# sp0256_dcf77.net
KiCad netlist of a schematic drawn in EAGLE
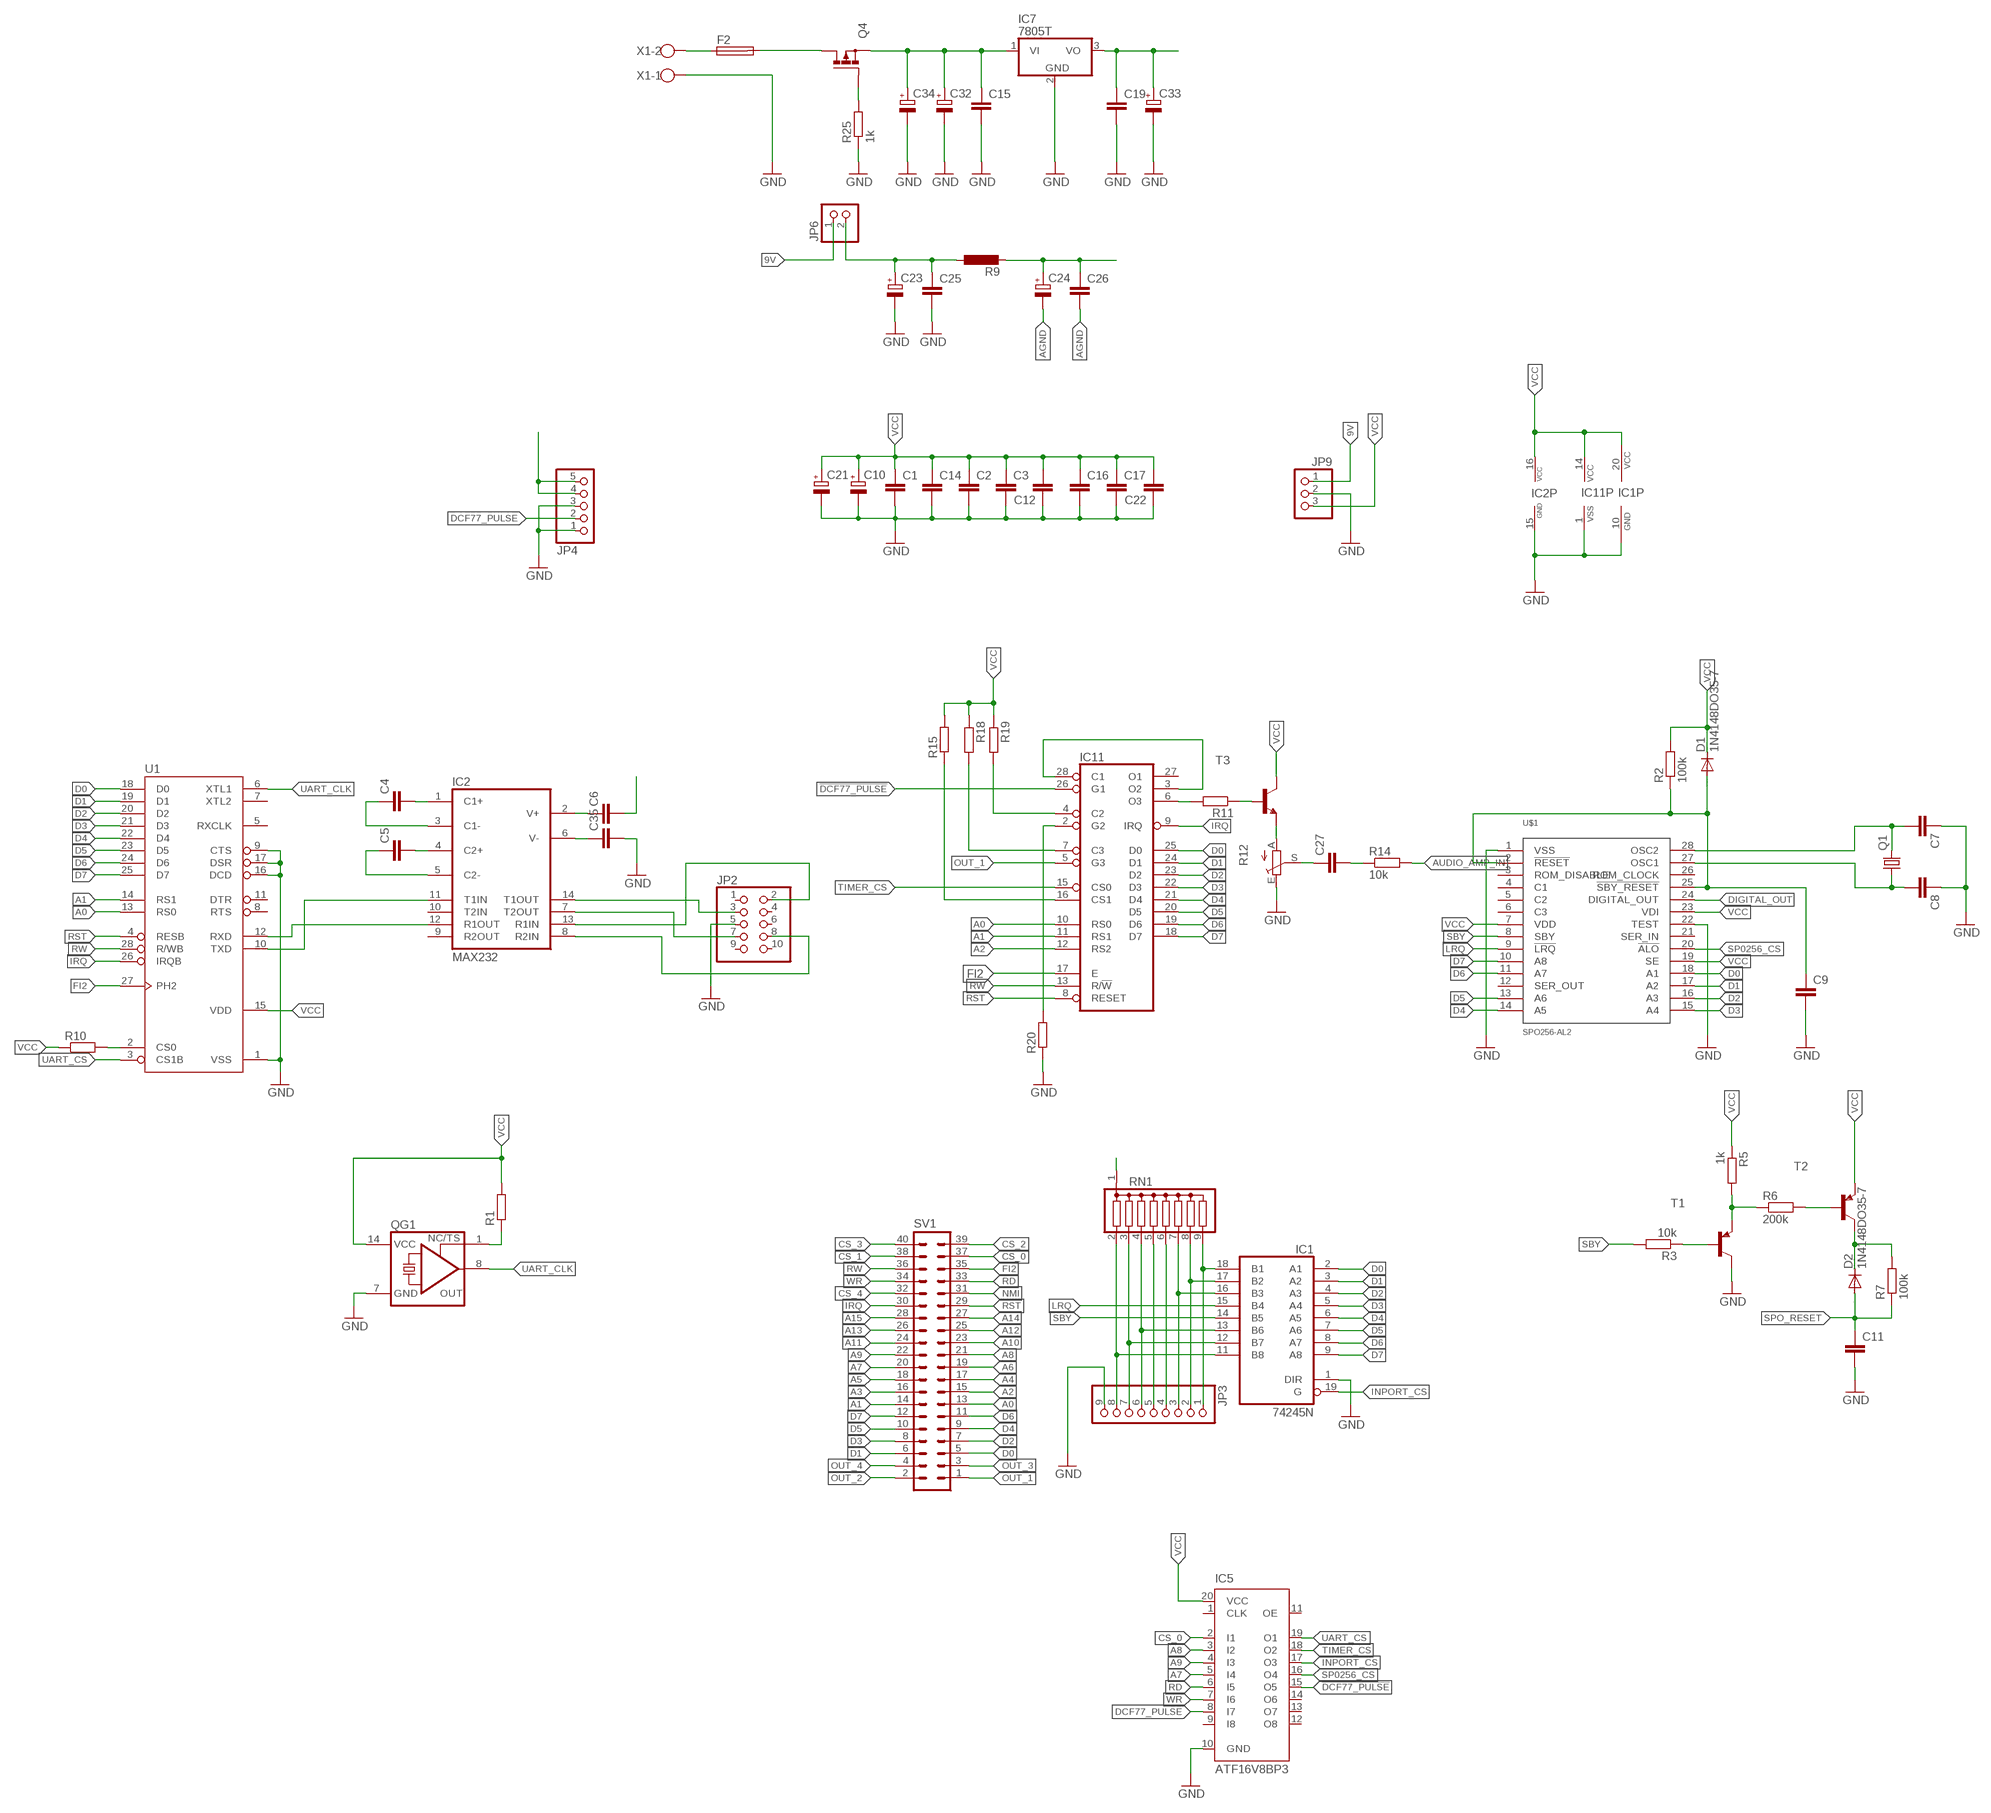
[diagram p0: schematic, sheet 1, part 1 of 2]
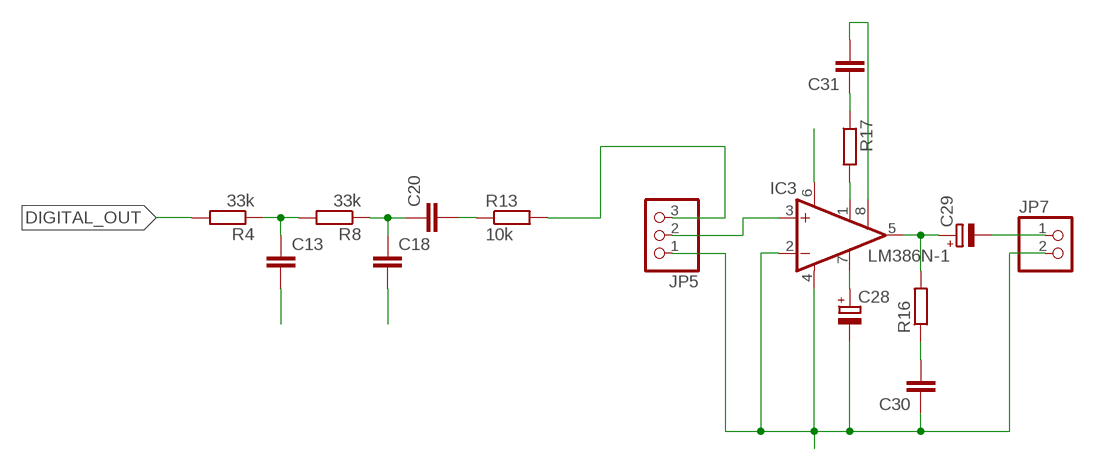
[diagram p1: schematic, sheet 1, part 2 of 2]

(export (version "E")
  (design (tool "Eeschema 10.0.6"))
  (components
    (comp (ref "C1")
      (value "C-EUC1206")
      (footprint "eagle-import:C1206")
      (libsource (lib "eagle-import") (part "C-EUC1206"))
    )
    (comp (ref "C2")
      (value "C-EUC1206")
      (footprint "eagle-import:C1206")
      (libsource (lib "eagle-import") (part "C-EUC1206"))
    )
    (comp (ref "C3")
      (value "C-EUC1206")
      (footprint "eagle-import:C1206")
      (libsource (lib "eagle-import") (part "C-EUC1206"))
    )
    (comp (ref "C4")
      (value "C-EUC0603")
      (footprint "eagle-import:C0603")
      (libsource (lib "eagle-import") (part "C-EUC0603"))
    )
    (comp (ref "C5")
      (value "C-EUC0603")
      (footprint "eagle-import:C0603")
      (libsource (lib "eagle-import") (part "C-EUC0603"))
    )
    (comp (ref "C6")
      (value "C-EUC0603")
      (footprint "eagle-import:C0603")
      (libsource (lib "eagle-import") (part "C-EUC0603"))
    )
    (comp (ref "C7")
      (value "C-EUC0603")
      (footprint "eagle-import:C0603")
      (libsource (lib "eagle-import") (part "C-EUC0603"))
    )
    (comp (ref "C8")
      (value "C-EUC0603")
      (footprint "eagle-import:C0603")
      (libsource (lib "eagle-import") (part "C-EUC0603"))
    )
    (comp (ref "C9")
      (value "C-EUC0603")
      (footprint "eagle-import:C0603")
      (libsource (lib "eagle-import") (part "C-EUC0603"))
    )
    (comp (ref "C10")
      (value "CPOL-EUE5-10.5")
      (footprint "eagle-import:E5-10,5")
      (libsource (lib "eagle-import") (part "CPOL-EUE5-10.5"))
    )
    (comp (ref "C11")
      (value "C-EUC0603")
      (footprint "eagle-import:C0603")
      (libsource (lib "eagle-import") (part "C-EUC0603"))
    )
    (comp (ref "C12")
      (value "C-EUC0603")
      (footprint "eagle-import:C0603")
      (libsource (lib "eagle-import") (part "C-EUC0603"))
    )
    (comp (ref "C13")
      (value "C-EUC0603")
      (footprint "eagle-import:C0603")
      (libsource (lib "eagle-import") (part "C-EUC0603"))
    )
    (comp (ref "C14")
      (value "C-EUC1206")
      (footprint "eagle-import:C1206")
      (libsource (lib "eagle-import") (part "C-EUC1206"))
    )
    (comp (ref "C15")
      (value "C-EUC1206")
      (footprint "eagle-import:C1206")
      (libsource (lib "eagle-import") (part "C-EUC1206"))
    )
    (comp (ref "C16")
      (value "C-EUC1206")
      (footprint "eagle-import:C1206")
      (libsource (lib "eagle-import") (part "C-EUC1206"))
    )
    (comp (ref "C17")
      (value "C-EUC1206")
      (footprint "eagle-import:C1206")
      (libsource (lib "eagle-import") (part "C-EUC1206"))
    )
    (comp (ref "C18")
      (value "C-EUC0603")
      (footprint "eagle-import:C0603")
      (libsource (lib "eagle-import") (part "C-EUC0603"))
    )
    (comp (ref "C19")
      (value "C-EUC1206")
      (footprint "eagle-import:C1206")
      (libsource (lib "eagle-import") (part "C-EUC1206"))
    )
    (comp (ref "C20")
      (value "C-EUC0603")
      (footprint "eagle-import:C0603")
      (libsource (lib "eagle-import") (part "C-EUC0603"))
    )
    (comp (ref "C21")
      (value "CPOL-EUSMCB")
      (footprint "eagle-import:SMC_B")
      (libsource (lib "eagle-import") (part "CPOL-EUSMCB"))
    )
    (comp (ref "C22")
      (value "C-EUC0603")
      (footprint "eagle-import:C0603")
      (libsource (lib "eagle-import") (part "C-EUC0603"))
    )
    (comp (ref "C23")
      (value "CPOL-EUE5-10.5")
      (footprint "eagle-import:E5-10,5")
      (libsource (lib "eagle-import") (part "CPOL-EUE5-10.5"))
    )
    (comp (ref "C24")
      (value "CPOL-EUE5-10.5")
      (footprint "eagle-import:E5-10,5")
      (libsource (lib "eagle-import") (part "CPOL-EUE5-10.5"))
    )
    (comp (ref "C25")
      (value "C-EUC1206")
      (footprint "eagle-import:C1206")
      (libsource (lib "eagle-import") (part "C-EUC1206"))
    )
    (comp (ref "C26")
      (value "C-EUC1206")
      (footprint "eagle-import:C1206")
      (libsource (lib "eagle-import") (part "C-EUC1206"))
    )
    (comp (ref "C27")
      (value "C-EUC0603")
      (footprint "eagle-import:C0603")
      (libsource (lib "eagle-import") (part "C-EUC0603"))
    )
    (comp (ref "C28")
      (value "CPOL-EUSMCB")
      (footprint "eagle-import:SMC_B")
      (libsource (lib "eagle-import") (part "CPOL-EUSMCB"))
    )
    (comp (ref "C29")
      (value "CPOL-EUE5-10.5")
      (footprint "eagle-import:E5-10,5")
      (libsource (lib "eagle-import") (part "CPOL-EUE5-10.5"))
    )
    (comp (ref "C30")
      (value "C-EUC0603")
      (footprint "eagle-import:C0603")
      (libsource (lib "eagle-import") (part "C-EUC0603"))
    )
    (comp (ref "C31")
      (value "C-EUC0603")
      (footprint "eagle-import:C0603")
      (libsource (lib "eagle-import") (part "C-EUC0603"))
    )
    (comp (ref "C32")
      (value "CPOL-EUE5-10.5")
      (footprint "eagle-import:E5-10,5")
      (libsource (lib "eagle-import") (part "CPOL-EUE5-10.5"))
    )
    (comp (ref "C33")
      (value "CPOL-EUE5-10.5")
      (footprint "eagle-import:E5-10,5")
      (libsource (lib "eagle-import") (part "CPOL-EUE5-10.5"))
    )
    (comp (ref "C34")
      (value "CPOL-EUE5-10.5")
      (footprint "eagle-import:E5-10,5")
      (libsource (lib "eagle-import") (part "CPOL-EUE5-10.5"))
    )
    (comp (ref "C35")
      (value "C-EUC0603")
      (footprint "eagle-import:C0603")
      (libsource (lib "eagle-import") (part "C-EUC0603"))
    )
    (comp (ref "D1")
      (value "1N4148DO35-7")
      (footprint "eagle-import:DO35-7")
      (libsource (lib "eagle-import") (part "1N4148DO35-7"))
    )
    (comp (ref "D2")
      (value "1N4148DO35-7")
      (footprint "eagle-import:DO35-7")
      (libsource (lib "eagle-import") (part "1N4148DO35-7"))
    )
    (comp (ref "F2")
      (value "SH22,5")
      (footprint "eagle-import:SH22,5")
      (fields
        (field (name "MF") "SCHURTER")
        (field (name "MPN") "0031.8201")
        (field (name "MF_1") "SCHURTER")
        (field (name "MPN_1") "0031.8201")
        (field (name "OC_FARNELL") "1162740")
        (field (name "OC_NEWARK") "96F8317")
      )
      (libsource (lib "eagle-import") (part "SH22,5"))
    )
    (comp (ref "IC1")
      (value "74245N")
      (footprint "eagle-import:DIL20")
      (libsource (lib "eagle-import") (part "74245NLS"))
    )
    (comp (ref "IC2")
      (value "MAX232")
      (footprint "eagle-import:DIL16")
      (fields (field (name "MF") "MAXIM") (field (name "MPN") "MAX232ACPE+"))
      (libsource (lib "eagle-import") (part "MAX232"))
    )
    (comp (ref "IC3")
      (value "LM386N-1")
      (footprint "eagle-import:DIL08")
      (libsource (lib "eagle-import") (part "LM386?-N1"))
    )
    (comp (ref "IC5")
      (value "ATF16V8BP3")
      (footprint "eagle-import:DIL20")
      (fields (field (name "MPN") "ATF16V8CZ-15PU"))
      (libsource (lib "eagle-import") (part "ATF16V8BP3"))
    )
    (comp (ref "IC7")
      (value "7805T")
      (footprint "eagle-import:TO220H")
      (libsource (lib "eagle-import") (part "78T05"))
    )
    (comp (ref "IC11")
      (value "6840")
      (footprint "eagle-import:DIL28")
      (libsource (lib "eagle-import") (part "6840"))
    )
    (comp (ref "JP2")
      (value "PINHD-2X5")
      (footprint "eagle-import:2X05")
      (libsource (lib "eagle-import") (part "PINHD-2X5"))
    )
    (comp (ref "JP3")
      (value "PINHD-1X9")
      (footprint "eagle-import:1X09")
      (libsource (lib "eagle-import") (part "PINHD-1X9"))
    )
    (comp (ref "JP4")
      (value "PINHD-1X5")
      (footprint "eagle-import:1X05")
      (libsource (lib "eagle-import") (part "PINHD-1X5"))
    )
    (comp (ref "JP5")
      (value "PINHD-1X3")
      (footprint "eagle-import:1X03")
      (libsource (lib "eagle-import") (part "PINHD-1X3"))
    )
    (comp (ref "JP6")
      (value "PINHD-1X2")
      (footprint "eagle-import:1X02")
      (libsource (lib "eagle-import") (part "PINHD-1X2"))
    )
    (comp (ref "JP7")
      (value "PINHD-1X2")
      (footprint "eagle-import:1X02")
      (libsource (lib "eagle-import") (part "PINHD-1X2"))
    )
    (comp (ref "JP9")
      (value "PINHD-1X3/90")
      (footprint "eagle-import:1X03_90")
      (libsource (lib "eagle-import") (part "PINHD-1X3/90"))
    )
    (comp (ref "Q1")
      (value "CRYSTALHC49U-V")
      (footprint "eagle-import:HC49U-V")
      (libsource (lib "eagle-import") (part "CRYSTALHC49U-V"))
    )
    (comp (ref "Q4")
      (value "P-MOSFET-SO8")
      (footprint "eagle-import:SO-08")
      (libsource (lib "eagle-import") (part "P-MOSFET-SO8"))
    )
    (comp (ref "QG1")
      (value "XO-14")
      (footprint "eagle-import:DIL14S")
      (libsource (lib "eagle-import") (part "XO-14"))
    )
    (comp (ref "R1")
      (value "R-EU_R1206")
      (footprint "eagle-import:R1206")
      (libsource (lib "eagle-import") (part "R-EU_R1206"))
    )
    (comp (ref "R2")
      (value "100k")
      (footprint "eagle-import:0204_7")
      (libsource (lib "eagle-import") (part "R-EU_0204/7"))
    )
    (comp (ref "R3")
      (value "10k")
      (footprint "eagle-import:0204_7")
      (libsource (lib "eagle-import") (part "R-EU_0204/7"))
    )
    (comp (ref "R4")
      (value "33k")
      (footprint "eagle-import:0204_7")
      (libsource (lib "eagle-import") (part "R-EU_0204/7"))
    )
    (comp (ref "R5")
      (value "1k")
      (footprint "eagle-import:0204_5")
      (libsource (lib "eagle-import") (part "R-EU_0204/5"))
    )
    (comp (ref "R6")
      (value "200k")
      (footprint "eagle-import:R0603")
      (libsource (lib "eagle-import") (part "R-EU_R0603"))
    )
    (comp (ref "R7")
      (value "100k")
      (footprint "eagle-import:0204_7")
      (libsource (lib "eagle-import") (part "R-EU_0204/7"))
    )
    (comp (ref "R8")
      (value "33k")
      (footprint "eagle-import:0204_7")
      (libsource (lib "eagle-import") (part "R-EU_0204/7"))
    )
    (comp (ref "R9")
      (value "L-EU0204/7")
      (footprint "eagle-import:0204_7")
      (libsource (lib "eagle-import") (part "L-EU0204/7"))
    )
    (comp (ref "R10")
      (value "R-EU_R0603")
      (footprint "eagle-import:R0603")
      (libsource (lib "eagle-import") (part "R-EU_R0603"))
    )
    (comp (ref "R11")
      (value "R-EU_0204/7")
      (footprint "eagle-import:0204_7")
      (libsource (lib "eagle-import") (part "R-EU_0204/7"))
    )
    (comp (ref "R12")
      (value "TRIM_EU-CA6V")
      (footprint "eagle-import:CA6V")
      (libsource (lib "eagle-import") (part "TRIM_EU-CA6V"))
    )
    (comp (ref "R13")
      (value "10k")
      (footprint "eagle-import:R0603")
      (libsource (lib "eagle-import") (part "R-EU_R0603"))
    )
    (comp (ref "R14")
      (value "10k")
      (footprint "eagle-import:R0603")
      (libsource (lib "eagle-import") (part "R-EU_R0603"))
    )
    (comp (ref "R15")
      (value "R-EU_R0603")
      (footprint "eagle-import:R0603")
      (libsource (lib "eagle-import") (part "R-EU_R0603"))
    )
    (comp (ref "R16")
      (value "R-EU_R0603")
      (footprint "eagle-import:R0603")
      (libsource (lib "eagle-import") (part "R-EU_R0603"))
    )
    (comp (ref "R17")
      (value "R-EU_0204/7")
      (footprint "eagle-import:0204_7")
      (libsource (lib "eagle-import") (part "R-EU_0204/7"))
    )
    (comp (ref "R18")
      (value "R-EU_R0603")
      (footprint "eagle-import:R0603")
      (libsource (lib "eagle-import") (part "R-EU_R0603"))
    )
    (comp (ref "R19")
      (value "R-EU_R0603")
      (footprint "eagle-import:R0603")
      (libsource (lib "eagle-import") (part "R-EU_R0603"))
    )
    (comp (ref "R20")
      (value "R-EU_R0603")
      (footprint "eagle-import:R0603")
      (libsource (lib "eagle-import") (part "R-EU_R0603"))
    )
    (comp (ref "R25")
      (value "1k")
      (footprint "eagle-import:R0603")
      (libsource (lib "eagle-import") (part "R-EU_R0603"))
    )
    (comp (ref "RN1")
      (value "G08R")
      (footprint "eagle-import:SIL9")
      (libsource (lib "eagle-import") (part "G08R"))
    )
    (comp (ref "SV1")
      (value "ML40L")
      (footprint "eagle-import:ML40L")
      (libsource (lib "eagle-import") (part "ML40L"))
    )
    (comp (ref "T1")
      (value "MPS2907A-PNP-TO92-CBE")
      (footprint "eagle-import:TO92-CBE")
      (libsource (lib "eagle-import") (part "-PNP-TO92-CBEMPS2907A"))
    )
    (comp (ref "T2")
      (value "MPS2907A-PNP-TO92-CBE")
      (footprint "eagle-import:TO92-CBE")
      (libsource (lib "eagle-import") (part "-PNP-TO92-CBEMPS2907A"))
    )
    (comp (ref "T3")
      (value "BC550-NPN-TO92-CBE")
      (footprint "eagle-import:TO92-CBE")
      (libsource (lib "eagle-import") (part "-NPN-TO92-CBEBC550"))
    )
    (comp (ref "U$1")
      (value "SPO256-AL2")
      (footprint "eagle-import:DIL28")
      (libsource (lib "eagle-import") (part "SPO256-AL2"))
    )
    (comp (ref "U1")
      (value "G65SC51P")
      (footprint "eagle-import:DIP-28")
      (libsource (lib "eagle-import") (part "G65SC51P"))
    )
    (comp (ref "X1")
      (value "W237-102")
      (footprint "eagle-import:W237-102")
      (fields (field (name "MPN") "237-102"))
      (libsource (lib "eagle-import") (part "W237-102"))
    )
  )
  (nets
    (net (code "1") (name "/AVCC") (class "Default")
      (node (ref "C24") (pin "+") (pinfunction "+_+") (pintype "passive"))
      (node (ref "C26") (pin "1") (pinfunction "1_1") (pintype "passive"))
      (node (ref "IC3") (pin "6") (pinfunction "VS_6") (pintype "power_in"))
      (node (ref "R9") (pin "2") (pinfunction "2_2") (pintype "passive"))
    )
    (net (code "2") (name "/~{DCF77_PULSE}") (class "Default")
      (node (ref "IC11") (pin "26") (pinfunction "G1_26") (pintype "input"))
      (node (ref "IC5") (pin "15") (pinfunction "O5_15") (pintype "output"))
    )
    (net (code "3") (name "9V") (class "Default")
      (node (ref "C15") (pin "1") (pinfunction "1_1") (pintype "passive"))
      (node (ref "C32") (pin "+") (pinfunction "+_+") (pintype "passive"))
      (node (ref "C34") (pin "+") (pinfunction "+_+") (pintype "passive"))
      (node (ref "IC7") (pin "1") (pinfunction "VI_1") (pintype "input"))
      (node (ref "JP6") (pin "1") (pinfunction "1_1") (pintype "passive"))
      (node (ref "JP9") (pin "1") (pinfunction "1_1") (pintype "passive"))
      (node (ref "Q4") (pin "1") (pinfunction "S_1") (pintype "passive"))
      (node (ref "Q4") (pin "2") (pinfunction "S_2") (pintype "passive"))
      (node (ref "Q4") (pin "3") (pinfunction "S_3") (pintype "passive"))
    )
    (net (code "4") (name "A0") (class "Default")
      (node (ref "IC11") (pin "10") (pinfunction "RS0_10") (pintype "input"))
      (node (ref "SV1") (pin "13") (pinfunction "13_13") (pintype "passive"))
      (node (ref "U1") (pin "13") (pinfunction "RS0_13") (pintype "input"))
    )
    (net (code "5") (name "A1") (class "Default")
      (node (ref "IC11") (pin "11") (pinfunction "RS1_11") (pintype "input"))
      (node (ref "SV1") (pin "14") (pinfunction "14_14") (pintype "passive"))
      (node (ref "U1") (pin "14") (pinfunction "RS1_14") (pintype "input"))
    )
    (net (code "6") (name "A2") (class "Default")
      (node (ref "IC11") (pin "12") (pinfunction "RS2_12") (pintype "input"))
      (node (ref "SV1") (pin "15") (pinfunction "15_15") (pintype "passive"))
    )
    (net (code "7") (name "A3") (class "Default")
      (node (ref "SV1") (pin "16") (pinfunction "16_16") (pintype "passive"))
    )
    (net (code "8") (name "A4") (class "Default")
      (node (ref "SV1") (pin "17") (pinfunction "17_17") (pintype "passive"))
    )
    (net (code "9") (name "A5") (class "Default")
      (node (ref "SV1") (pin "18") (pinfunction "18_18") (pintype "passive"))
    )
    (net (code "10") (name "A6") (class "Default")
      (node (ref "SV1") (pin "19") (pinfunction "19_19") (pintype "passive"))
    )
    (net (code "11") (name "A7") (class "Default")
      (node (ref "IC5") (pin "5") (pinfunction "I4_5") (pintype "input"))
      (node (ref "SV1") (pin "20") (pinfunction "20_20") (pintype "passive"))
    )
    (net (code "12") (name "A8") (class "Default")
      (node (ref "IC5") (pin "3") (pinfunction "I2_3") (pintype "input"))
      (node (ref "SV1") (pin "21") (pinfunction "21_21") (pintype "passive"))
    )
    (net (code "13") (name "A9") (class "Default")
      (node (ref "IC5") (pin "4") (pinfunction "I3_4") (pintype "input"))
      (node (ref "SV1") (pin "22") (pinfunction "22_22") (pintype "passive"))
    )
    (net (code "14") (name "A10") (class "Default")
      (node (ref "SV1") (pin "23") (pinfunction "23_23") (pintype "passive"))
    )
    (net (code "15") (name "A11") (class "Default")
      (node (ref "SV1") (pin "24") (pinfunction "24_24") (pintype "passive"))
    )
    (net (code "16") (name "A12") (class "Default")
      (node (ref "SV1") (pin "25") (pinfunction "25_25") (pintype "passive"))
    )
    (net (code "17") (name "A13") (class "Default")
      (node (ref "SV1") (pin "26") (pinfunction "26_26") (pintype "passive"))
    )
    (net (code "18") (name "A14") (class "Default")
      (node (ref "SV1") (pin "27") (pinfunction "27_27") (pintype "passive"))
    )
    (net (code "19") (name "A15") (class "Default")
      (node (ref "SV1") (pin "28") (pinfunction "28_28") (pintype "passive"))
    )
    (net (code "20") (name "AGND") (class "Default")
      (node (ref "C13") (pin "2") (pinfunction "2_2") (pintype "passive"))
      (node (ref "C18") (pin "2") (pinfunction "2_2") (pintype "passive"))
      (node (ref "C24") (pin "-") (pinfunction "-_-") (pintype "passive"))
      (node (ref "C26") (pin "2") (pinfunction "2_2") (pintype "passive"))
      (node (ref "C28") (pin "-") (pinfunction "-_-") (pintype "passive"))
      (node (ref "C30") (pin "1") (pinfunction "1_1") (pintype "passive"))
      (node (ref "IC3") (pin "2") (pinfunction "-IN_2") (pintype "input"))
      (node (ref "IC3") (pin "4") (pinfunction "GND_4") (pintype "power_in"))
      (node (ref "JP5") (pin "1") (pinfunction "1_1") (pintype "passive"))
      (node (ref "JP7") (pin "2") (pinfunction "2_2") (pintype "passive"))
    )
    (net (code "21") (name "AUDIO_AMP_IN") (class "Default")
      (node (ref "JP5") (pin "3") (pinfunction "3_3") (pintype "passive"))
      (node (ref "R13") (pin "2") (pinfunction "2_2") (pintype "passive"))
      (node (ref "R14") (pin "2") (pinfunction "2_2") (pintype "passive"))
    )
    (net (code "22") (name "CS_0") (class "Default")
      (node (ref "IC5") (pin "2") (pinfunction "I1_2") (pintype "input"))
      (node (ref "SV1") (pin "37") (pinfunction "37_37") (pintype "passive"))
    )
    (net (code "23") (name "CS_1") (class "Default")
      (node (ref "SV1") (pin "38") (pinfunction "38_38") (pintype "passive"))
    )
    (net (code "24") (name "CS_2") (class "Default")
      (node (ref "SV1") (pin "39") (pinfunction "39_39") (pintype "passive"))
    )
    (net (code "25") (name "CS_3") (class "Default")
      (node (ref "SV1") (pin "40") (pinfunction "40_40") (pintype "passive"))
    )
    (net (code "26") (name "CS_4") (class "Default")
      (node (ref "SV1") (pin "32") (pinfunction "32_32") (pintype "passive"))
    )
    (net (code "27") (name "D0") (class "Default")
      (node (ref "IC1") (pin "2") (pinfunction "A1_2") (pintype "bidirectional"))
      (node (ref "IC11") (pin "25") (pinfunction "D0_25") (pintype "bidirectional"))
      (node (ref "SV1") (pin "5") (pinfunction "5_5") (pintype "passive"))
      (node (ref "U$1") (pin "18") (pinfunction "A1_18") (pintype "bidirectional"))
      (node (ref "U1") (pin "18") (pinfunction "D0_18") (pintype "bidirectional"))
    )
    (net (code "28") (name "D1") (class "Default")
      (node (ref "IC1") (pin "3") (pinfunction "A2_3") (pintype "bidirectional"))
      (node (ref "IC11") (pin "24") (pinfunction "D1_24") (pintype "bidirectional"))
      (node (ref "SV1") (pin "6") (pinfunction "6_6") (pintype "passive"))
      (node (ref "U$1") (pin "17") (pinfunction "A2_17") (pintype "bidirectional"))
      (node (ref "U1") (pin "19") (pinfunction "D1_19") (pintype "bidirectional"))
    )
    (net (code "29") (name "D2") (class "Default")
      (node (ref "IC1") (pin "4") (pinfunction "A3_4") (pintype "bidirectional"))
      (node (ref "IC11") (pin "23") (pinfunction "D2_23") (pintype "bidirectional"))
      (node (ref "SV1") (pin "7") (pinfunction "7_7") (pintype "passive"))
      (node (ref "U$1") (pin "16") (pinfunction "A3_16") (pintype "bidirectional"))
      (node (ref "U1") (pin "20") (pinfunction "D2_20") (pintype "bidirectional"))
    )
    (net (code "30") (name "D3") (class "Default")
      (node (ref "IC1") (pin "5") (pinfunction "A4_5") (pintype "bidirectional"))
      (node (ref "IC11") (pin "22") (pinfunction "D3_22") (pintype "bidirectional"))
      (node (ref "SV1") (pin "8") (pinfunction "8_8") (pintype "passive"))
      (node (ref "U$1") (pin "15") (pinfunction "A4_15") (pintype "bidirectional"))
      (node (ref "U1") (pin "21") (pinfunction "D3_21") (pintype "bidirectional"))
    )
    (net (code "31") (name "D4") (class "Default")
      (node (ref "IC1") (pin "6") (pinfunction "A5_6") (pintype "bidirectional"))
      (node (ref "IC11") (pin "21") (pinfunction "D4_21") (pintype "bidirectional"))
      (node (ref "SV1") (pin "9") (pinfunction "9_9") (pintype "passive"))
      (node (ref "U$1") (pin "14") (pinfunction "A5_14") (pintype "bidirectional"))
      (node (ref "U1") (pin "22") (pinfunction "D4_22") (pintype "bidirectional"))
    )
    (net (code "32") (name "D5") (class "Default")
      (node (ref "IC1") (pin "7") (pinfunction "A6_7") (pintype "bidirectional"))
      (node (ref "IC11") (pin "20") (pinfunction "D5_20") (pintype "bidirectional"))
      (node (ref "SV1") (pin "10") (pinfunction "10_10") (pintype "passive"))
      (node (ref "U$1") (pin "13") (pinfunction "A6_13") (pintype "bidirectional"))
      (node (ref "U1") (pin "23") (pinfunction "D5_23") (pintype "bidirectional"))
    )
    (net (code "33") (name "D6") (class "Default")
      (node (ref "IC1") (pin "8") (pinfunction "A7_8") (pintype "bidirectional"))
      (node (ref "IC11") (pin "19") (pinfunction "D6_19") (pintype "bidirectional"))
      (node (ref "SV1") (pin "11") (pinfunction "11_11") (pintype "passive"))
      (node (ref "U$1") (pin "11") (pinfunction "A7_11") (pintype "bidirectional"))
      (node (ref "U1") (pin "24") (pinfunction "D6_24") (pintype "bidirectional"))
    )
    (net (code "34") (name "D7") (class "Default")
      (node (ref "IC1") (pin "9") (pinfunction "A8_9") (pintype "bidirectional"))
      (node (ref "IC11") (pin "18") (pinfunction "D7_18") (pintype "bidirectional"))
      (node (ref "SV1") (pin "12") (pinfunction "12_12") (pintype "passive"))
      (node (ref "U$1") (pin "10") (pinfunction "A8_10") (pintype "bidirectional"))
      (node (ref "U1") (pin "25") (pinfunction "D7_25") (pintype "bidirectional"))
    )
    (net (code "35") (name "DCF77_PULSE") (class "Default")
      (node (ref "IC5") (pin "8") (pinfunction "I7_8") (pintype "input"))
      (node (ref "JP4") (pin "2") (pinfunction "2_2") (pintype "passive"))
    )
    (net (code "36") (name "DIGITAL_OUT") (class "Default")
      (node (ref "R4") (pin "2") (pinfunction "2_2") (pintype "passive"))
      (node (ref "U$1") (pin "24") (pinfunction "DIGITAL_OUT_24") (pintype "bidirectional"))
    )
    (net (code "37") (name "FI2") (class "Default")
      (node (ref "IC11") (pin "17") (pinfunction "E_17") (pintype "input"))
      (node (ref "SV1") (pin "35") (pinfunction "35_35") (pintype "passive"))
      (node (ref "U1") (pin "27") (pinfunction "PH2_27") (pintype "power_in"))
    )
    (net (code "38") (name "GND") (class "Default")
      (node (ref "C1") (pin "2") (pinfunction "2_2") (pintype "passive"))
      (node (ref "C10") (pin "-") (pinfunction "-_-") (pintype "passive"))
      (node (ref "C11") (pin "2") (pinfunction "2_2") (pintype "passive"))
      (node (ref "C12") (pin "1") (pinfunction "1_1") (pintype "passive"))
      (node (ref "C14") (pin "2") (pinfunction "2_2") (pintype "passive"))
      (node (ref "C15") (pin "2") (pinfunction "2_2") (pintype "passive"))
      (node (ref "C16") (pin "2") (pinfunction "2_2") (pintype "passive"))
      (node (ref "C17") (pin "2") (pinfunction "2_2") (pintype "passive"))
      (node (ref "C19") (pin "2") (pinfunction "2_2") (pintype "passive"))
      (node (ref "C2") (pin "2") (pinfunction "2_2") (pintype "passive"))
      (node (ref "C21") (pin "-") (pinfunction "-_-") (pintype "passive"))
      (node (ref "C22") (pin "1") (pinfunction "1_1") (pintype "passive"))
      (node (ref "C23") (pin "-") (pinfunction "-_-") (pintype "passive"))
      (node (ref "C25") (pin "2") (pinfunction "2_2") (pintype "passive"))
      (node (ref "C3") (pin "2") (pinfunction "2_2") (pintype "passive"))
      (node (ref "C32") (pin "-") (pinfunction "-_-") (pintype "passive"))
      (node (ref "C33") (pin "-") (pinfunction "-_-") (pintype "passive"))
      (node (ref "C34") (pin "-") (pinfunction "-_-") (pintype "passive"))
      (node (ref "C35") (pin "2") (pinfunction "2_2") (pintype "passive"))
      (node (ref "C7") (pin "1") (pinfunction "1_1") (pintype "passive"))
      (node (ref "C8") (pin "1") (pinfunction "1_1") (pintype "passive"))
      (node (ref "C9") (pin "2") (pinfunction "2_2") (pintype "passive"))
      (node (ref "IC1") (pin "1") (pinfunction "DIR_1") (pintype "input"))
      (node (ref "IC1") (pin "10") (pinfunction "GND_10") (pintype "power_in"))
      (node (ref "IC11") (pin "1") (pinfunction "VSS_1") (pintype "power_in"))
      (node (ref "IC2") (pin "15") (pinfunction "GND_15") (pintype "power_in"))
      (node (ref "IC5") (pin "10") (pinfunction "GND_10") (pintype "power_in"))
      (node (ref "IC7") (pin "2") (pinfunction "GND_2") (pintype "passive"))
      (node (ref "JP2") (pin "5") (pinfunction "5_5") (pintype "passive"))
      (node (ref "JP3") (pin "9") (pinfunction "9_9") (pintype "passive"))
      (node (ref "JP4") (pin "1") (pinfunction "1_1") (pintype "passive"))
      (node (ref "JP4") (pin "3") (pinfunction "3_3") (pintype "passive"))
      (node (ref "JP9") (pin "2") (pinfunction "2_2") (pintype "passive"))
      (node (ref "QG1") (pin "7") (pinfunction "GND_7") (pintype "power_in"))
      (node (ref "R12") (pin "E") (pinfunction "E_E") (pintype "passive"))
      (node (ref "R20") (pin "1") (pinfunction "1_1") (pintype "passive"))
      (node (ref "R25") (pin "1") (pinfunction "1_1") (pintype "passive"))
      (node (ref "T1") (pin "C") (pinfunction "C_C") (pintype "passive"))
      (node (ref "U$1") (pin "1") (pinfunction "VSS_1") (pintype "bidirectional"))
      (node (ref "U$1") (pin "22") (pinfunction "TEST_22") (pintype "bidirectional"))
      (node (ref "U1") (pin "1") (pinfunction "VSS_1") (pintype "power_in"))
      (node (ref "U1") (pin "16") (pinfunction "DCD_16") (pintype "input"))
      (node (ref "U1") (pin "17") (pinfunction "DSR_17") (pintype "input"))
      (node (ref "U1") (pin "9") (pinfunction "CTS_9") (pintype "input"))
      (node (ref "X1") (pin "1") (pinfunction "KL_1") (pintype "passive"))
    )
    (net (code "39") (name "INPORT_CS") (class "Default")
      (node (ref "IC1") (pin "19") (pinfunction "G_19") (pintype "input"))
      (node (ref "IC5") (pin "17") (pinfunction "O3_17") (pintype "output"))
    )
    (net (code "40") (name "IRQ") (class "Default")
      (node (ref "IC11") (pin "9") (pinfunction "IRQ_9") (pintype "open_collector"))
      (node (ref "SV1") (pin "30") (pinfunction "30_30") (pintype "passive"))
      (node (ref "U1") (pin "26") (pinfunction "IRQB_26") (pintype "output"))
    )
    (net (code "41") (name "LRQ") (class "Default")
      (node (ref "IC1") (pin "15") (pinfunction "B4_15") (pintype "bidirectional"))
      (node (ref "U$1") (pin "9") (pinfunction "~{LRQ}_9") (pintype "bidirectional"))
    )
    (net (code "42") (name "NMI") (class "Default")
      (node (ref "SV1") (pin "31") (pinfunction "31_31") (pintype "passive"))
    )
    (net (code "43") (name "Net-(C13-Pad1)") (class "Default")
      (node (ref "C13") (pin "1") (pinfunction "1_1") (pintype "passive"))
      (node (ref "R4") (pin "1") (pinfunction "1_1") (pintype "passive"))
      (node (ref "R8") (pin "2") (pinfunction "2_2") (pintype "passive"))
    )
    (net (code "44") (name "Net-(C18-Pad1)") (class "Default")
      (node (ref "C18") (pin "1") (pinfunction "1_1") (pintype "passive"))
      (node (ref "C20") (pin "1") (pinfunction "1_1") (pintype "passive"))
      (node (ref "R8") (pin "1") (pinfunction "1_1") (pintype "passive"))
    )
    (net (code "45") (name "Net-(C20-Pad2)") (class "Default")
      (node (ref "C20") (pin "2") (pinfunction "2_2") (pintype "passive"))
      (node (ref "R13") (pin "1") (pinfunction "1_1") (pintype "passive"))
    )
    (net (code "46") (name "Net-(C23-Pad+)") (class "Default")
      (node (ref "C23") (pin "+") (pinfunction "+_+") (pintype "passive"))
      (node (ref "C25") (pin "1") (pinfunction "1_1") (pintype "passive"))
      (node (ref "JP6") (pin "2") (pinfunction "2_2") (pintype "passive"))
      (node (ref "R9") (pin "1") (pinfunction "1_1") (pintype "passive"))
    )
    (net (code "47") (name "Net-(C27-Pad1)") (class "Default")
      (node (ref "C27") (pin "1") (pinfunction "1_1") (pintype "passive"))
      (node (ref "R12") (pin "S") (pinfunction "S_S") (pintype "passive"))
    )
    (net (code "48") (name "Net-(C27-Pad2)") (class "Default")
      (node (ref "C27") (pin "2") (pinfunction "2_2") (pintype "passive"))
      (node (ref "R14") (pin "1") (pinfunction "1_1") (pintype "passive"))
    )
    (net (code "49") (name "Net-(C29-Pad-)") (class "Default")
      (node (ref "C29") (pin "-") (pinfunction "-_-") (pintype "passive"))
      (node (ref "JP7") (pin "1") (pinfunction "1_1") (pintype "passive"))
    )
    (net (code "50") (name "Net-(C30-Pad2)") (class "Default")
      (node (ref "C30") (pin "2") (pinfunction "2_2") (pintype "passive"))
      (node (ref "R16") (pin "1") (pinfunction "1_1") (pintype "passive"))
    )
    (net (code "51") (name "Net-(C31-Pad1)") (class "Default")
      (node (ref "C31") (pin "1") (pinfunction "1_1") (pintype "passive"))
      (node (ref "R17") (pin "1") (pinfunction "1_1") (pintype "passive"))
    )
    (net (code "52") (name "Net-(C31-Pad2)") (class "Default")
      (node (ref "C31") (pin "2") (pinfunction "2_2") (pintype "passive"))
      (node (ref "IC3") (pin "8") (pinfunction "GAIN_8") (pintype "passive"))
    )
    (net (code "53") (name "Net-(D2-PadC)") (class "Default")
      (node (ref "D2") (pin "C") (pinfunction "C_C") (pintype "passive"))
      (node (ref "R7") (pin "2") (pinfunction "2_2") (pintype "passive"))
      (node (ref "T2") (pin "C") (pinfunction "C_C") (pintype "passive"))
    )
    (net (code "54") (name "Net-(F2-Pad2)") (class "Default")
      (node (ref "F2") (pin "2") (pinfunction "2_2") (pintype "passive"))
      (node (ref "Q4") (pin "5") (pinfunction "D_5") (pintype "passive"))
      (node (ref "Q4") (pin "6") (pinfunction "D_6") (pintype "passive"))
      (node (ref "Q4") (pin "7") (pinfunction "D_7") (pintype "passive"))
      (node (ref "Q4") (pin "8") (pinfunction "D_8") (pintype "passive"))
    )
    (net (code "55") (name "Net-(IC1A-B1)") (class "Default")
      (node (ref "IC1") (pin "18") (pinfunction "B1_18") (pintype "bidirectional"))
      (node (ref "JP3") (pin "1") (pinfunction "1_1") (pintype "passive"))
      (node (ref "RN1") (pin "9") (pinfunction "9_9") (pintype "passive"))
    )
    (net (code "56") (name "Net-(IC1A-B2)") (class "Default")
      (node (ref "IC1") (pin "17") (pinfunction "B2_17") (pintype "bidirectional"))
      (node (ref "JP3") (pin "2") (pinfunction "2_2") (pintype "passive"))
      (node (ref "RN1") (pin "8") (pinfunction "8_8") (pintype "passive"))
    )
    (net (code "57") (name "Net-(IC1A-B3)") (class "Default")
      (node (ref "IC1") (pin "16") (pinfunction "B3_16") (pintype "bidirectional"))
      (node (ref "JP3") (pin "3") (pinfunction "3_3") (pintype "passive"))
      (node (ref "RN1") (pin "7") (pinfunction "7_7") (pintype "passive"))
    )
    (net (code "58") (name "Net-(IC1A-B6)") (class "Default")
      (node (ref "IC1") (pin "13") (pinfunction "B6_13") (pintype "bidirectional"))
      (node (ref "JP3") (pin "6") (pinfunction "6_6") (pintype "passive"))
      (node (ref "RN1") (pin "4") (pinfunction "4_4") (pintype "passive"))
    )
    (net (code "59") (name "Net-(IC1A-B7)") (class "Default")
      (node (ref "IC1") (pin "12") (pinfunction "B7_12") (pintype "bidirectional"))
      (node (ref "JP3") (pin "7") (pinfunction "7_7") (pintype "passive"))
      (node (ref "RN1") (pin "3") (pinfunction "3_3") (pintype "passive"))
    )
    (net (code "60") (name "Net-(IC1A-B8)") (class "Default")
      (node (ref "IC1") (pin "11") (pinfunction "B8_11") (pintype "bidirectional"))
      (node (ref "JP3") (pin "8") (pinfunction "8_8") (pintype "passive"))
      (node (ref "RN1") (pin "2") (pinfunction "2_2") (pintype "passive"))
    )
    (net (code "61") (name "Net-(IC2A-C1+)") (class "Default")
      (node (ref "C4") (pin "2") (pinfunction "2_2") (pintype "passive"))
      (node (ref "IC2") (pin "1") (pinfunction "C1+_1") (pintype "bidirectional"))
    )
    (net (code "62") (name "Net-(IC2A-C1-)") (class "Default")
      (node (ref "C4") (pin "1") (pinfunction "1_1") (pintype "passive"))
      (node (ref "IC2") (pin "3") (pinfunction "C1-_3") (pintype "bidirectional"))
    )
    (net (code "63") (name "Net-(IC2A-C2+)") (class "Default")
      (node (ref "C5") (pin "2") (pinfunction "2_2") (pintype "passive"))
      (node (ref "IC2") (pin "4") (pinfunction "C2+_4") (pintype "bidirectional"))
    )
    (net (code "64") (name "Net-(IC2A-C2-)") (class "Default")
      (node (ref "C5") (pin "1") (pinfunction "1_1") (pintype "passive"))
      (node (ref "IC2") (pin "5") (pinfunction "C2-_5") (pintype "bidirectional"))
    )
    (net (code "65") (name "Net-(IC2A-R1IN)") (class "Default")
      (node (ref "IC2") (pin "13") (pinfunction "R1IN_13") (pintype "input"))
      (node (ref "JP2") (pin "2") (pinfunction "2_2") (pintype "passive"))
    )
    (net (code "66") (name "Net-(IC2A-R1OUT)") (class "Default")
      (node (ref "IC2") (pin "12") (pinfunction "R1OUT_12") (pintype "output"))
      (node (ref "U1") (pin "12") (pinfunction "RXD_12") (pintype "input"))
    )
    (net (code "67") (name "Net-(IC2A-R2IN)") (class "Default")
      (node (ref "IC2") (pin "8") (pinfunction "R2IN_8") (pintype "input"))
      (node (ref "JP2") (pin "8") (pinfunction "8_8") (pintype "passive"))
    )
    (net (code "68") (name "Net-(IC2A-T1IN)") (class "Default")
      (node (ref "IC2") (pin "11") (pinfunction "T1IN_11") (pintype "input"))
      (node (ref "U1") (pin "10") (pinfunction "TXD_10") (pintype "output"))
    )
    (net (code "69") (name "Net-(IC2A-T1OUT)") (class "Default")
      (node (ref "IC2") (pin "14") (pinfunction "T1OUT_14") (pintype "output"))
      (node (ref "JP2") (pin "3") (pinfunction "3_3") (pintype "passive"))
    )
    (net (code "70") (name "Net-(IC2A-T2OUT)") (class "Default")
      (node (ref "IC2") (pin "7") (pinfunction "T2OUT_7") (pintype "output"))
      (node (ref "JP2") (pin "7") (pinfunction "7_7") (pintype "passive"))
    )
    (net (code "71") (name "Net-(IC2A-V+)") (class "Default")
      (node (ref "C6") (pin "1") (pinfunction "1_1") (pintype "passive"))
      (node (ref "IC2") (pin "2") (pinfunction "V+_2") (pintype "bidirectional"))
    )
    (net (code "72") (name "Net-(IC2A-V-)") (class "Default")
      (node (ref "C35") (pin "1") (pinfunction "1_1") (pintype "passive"))
      (node (ref "IC2") (pin "6") (pinfunction "V-_6") (pintype "bidirectional"))
    )
    (net (code "73") (name "Net-(IC3-+IN)") (class "Default")
      (node (ref "IC3") (pin "3") (pinfunction "+IN_3") (pintype "input"))
      (node (ref "JP5") (pin "2") (pinfunction "2_2") (pintype "passive"))
    )
    (net (code "74") (name "Net-(IC3-BYPASS)") (class "Default")
      (node (ref "C28") (pin "+") (pinfunction "+_+") (pintype "passive"))
      (node (ref "IC3") (pin "7") (pinfunction "BYPASS_7") (pintype "passive"))
    )
    (net (code "75") (name "Net-(IC3-GAIN-Pad1)") (class "Default")
      (node (ref "IC3") (pin "1") (pinfunction "GAIN_1") (pintype "passive"))
      (node (ref "R17") (pin "2") (pinfunction "2_2") (pintype "passive"))
    )
    (net (code "76") (name "Net-(IC3-OUT)") (class "Default")
      (node (ref "C29") (pin "+") (pinfunction "+_+") (pintype "passive"))
      (node (ref "IC3") (pin "5") (pinfunction "OUT_5") (pintype "output"))
      (node (ref "R16") (pin "2") (pinfunction "2_2") (pintype "passive"))
    )
    (net (code "77") (name "Net-(IC11A-C1)") (class "Default")
      (node (ref "IC11") (pin "28") (pinfunction "C1_28") (pintype "input"))
      (node (ref "IC11") (pin "3") (pinfunction "O2_3") (pintype "output"))
    )
    (net (code "78") (name "Net-(IC11A-C2)") (class "Default")
      (node (ref "IC11") (pin "4") (pinfunction "C2_4") (pintype "input"))
      (node (ref "R19") (pin "2") (pinfunction "2_2") (pintype "passive"))
    )
    (net (code "79") (name "Net-(IC11A-C3)") (class "Default")
      (node (ref "IC11") (pin "7") (pinfunction "C3_7") (pintype "input"))
      (node (ref "R18") (pin "2") (pinfunction "2_2") (pintype "passive"))
    )
    (net (code "80") (name "Net-(IC11A-CS1)") (class "Default")
      (node (ref "IC11") (pin "16") (pinfunction "CS1_16") (pintype "input"))
      (node (ref "R15") (pin "1") (pinfunction "1_1") (pintype "passive"))
    )
    (net (code "81") (name "Net-(IC11A-G2)") (class "Default")
      (node (ref "IC11") (pin "2") (pinfunction "G2_2") (pintype "input"))
      (node (ref "R20") (pin "2") (pinfunction "2_2") (pintype "passive"))
    )
    (net (code "82") (name "Net-(IC11A-O3)") (class "Default")
      (node (ref "IC11") (pin "6") (pinfunction "O3_6") (pintype "output"))
      (node (ref "R11") (pin "2") (pinfunction "2_2") (pintype "passive"))
    )
    (net (code "83") (name "Net-(JP3-Pad4)") (class "Default")
      (node (ref "JP3") (pin "4") (pinfunction "4_4") (pintype "passive"))
      (node (ref "RN1") (pin "6") (pinfunction "6_6") (pintype "passive"))
    )
    (net (code "84") (name "Net-(JP3-Pad5)") (class "Default")
      (node (ref "JP3") (pin "5") (pinfunction "5_5") (pintype "passive"))
      (node (ref "RN1") (pin "5") (pinfunction "5_5") (pintype "passive"))
    )
    (net (code "85") (name "Net-(Q4-G)") (class "Default")
      (node (ref "Q4") (pin "4") (pinfunction "G_4") (pintype "passive"))
      (node (ref "R25") (pin "2") (pinfunction "2_2") (pintype "passive"))
    )
    (net (code "86") (name "Net-(QG1-TS)") (class "Default")
      (node (ref "QG1") (pin "1") (pinfunction "TS_1") (pintype "passive"))
      (node (ref "R1") (pin "1") (pinfunction "1_1") (pintype "passive"))
    )
    (net (code "87") (name "Net-(R3-Pad1)") (class "Default")
      (node (ref "R3") (pin "1") (pinfunction "1_1") (pintype "passive"))
      (node (ref "T1") (pin "B") (pinfunction "B_B") (pintype "passive"))
    )
    (net (code "88") (name "Net-(R5-Pad2)") (class "Default")
      (node (ref "R5") (pin "2") (pinfunction "2_2") (pintype "passive"))
      (node (ref "R6") (pin "1") (pinfunction "1_1") (pintype "passive"))
      (node (ref "T1") (pin "E") (pinfunction "E_E") (pintype "passive"))
    )
    (net (code "89") (name "Net-(R6-Pad2)") (class "Default")
      (node (ref "R6") (pin "2") (pinfunction "2_2") (pintype "passive"))
      (node (ref "T2") (pin "B") (pinfunction "B_B") (pintype "passive"))
    )
    (net (code "90") (name "Net-(R11-Pad1)") (class "Default")
      (node (ref "R11") (pin "1") (pinfunction "1_1") (pintype "passive"))
      (node (ref "T3") (pin "B") (pinfunction "B_B") (pintype "passive"))
    )
    (net (code "91") (name "Net-(R12-PadA)") (class "Default")
      (node (ref "R12") (pin "A") (pinfunction "A_A") (pintype "passive"))
      (node (ref "T3") (pin "E") (pinfunction "E_E") (pintype "passive"))
    )
    (net (code "92") (name "Net-(U$1-OSC1)") (class "Default")
      (node (ref "C8") (pin "2") (pinfunction "2_2") (pintype "passive"))
      (node (ref "Q1") (pin "1") (pinfunction "1_1") (pintype "passive"))
      (node (ref "U$1") (pin "27") (pinfunction "OSC1_27") (pintype "bidirectional"))
    )
    (net (code "93") (name "Net-(U$1-OSC2)") (class "Default")
      (node (ref "C7") (pin "2") (pinfunction "2_2") (pintype "passive"))
      (node (ref "Q1") (pin "2") (pinfunction "2_2") (pintype "passive"))
      (node (ref "U$1") (pin "28") (pinfunction "OSC2_28") (pintype "bidirectional"))
    )
    (net (code "94") (name "Net-(U1-CS0)") (class "Default")
      (node (ref "R10") (pin "2") (pinfunction "2_2") (pintype "passive"))
      (node (ref "U1") (pin "2") (pinfunction "CS0_2") (pintype "input"))
    )
    (net (code "95") (name "Net-(X1B-KL)") (class "Default")
      (node (ref "F2") (pin "1") (pinfunction "1_1") (pintype "passive"))
      (node (ref "X1") (pin "2") (pinfunction "KL_2") (pintype "passive"))
    )
    (net (code "96") (name "OUT_1") (class "Default")
      (node (ref "IC11") (pin "5") (pinfunction "G3_5") (pintype "input"))
      (node (ref "SV1") (pin "1") (pinfunction "1_1") (pintype "passive"))
    )
    (net (code "97") (name "OUT_2") (class "Default")
      (node (ref "SV1") (pin "2") (pinfunction "2_2") (pintype "passive"))
    )
    (net (code "98") (name "OUT_3") (class "Default")
      (node (ref "SV1") (pin "3") (pinfunction "3_3") (pintype "passive"))
    )
    (net (code "99") (name "OUT_4") (class "Default")
      (node (ref "SV1") (pin "4") (pinfunction "4_4") (pintype "passive"))
    )
    (net (code "100") (name "RD") (class "Default")
      (node (ref "IC5") (pin "6") (pinfunction "I5_6") (pintype "input"))
      (node (ref "SV1") (pin "33") (pinfunction "33_33") (pintype "passive"))
    )
    (net (code "101") (name "RST") (class "Default")
      (node (ref "IC11") (pin "8") (pinfunction "RESET_8") (pintype "input"))
      (node (ref "SV1") (pin "29") (pinfunction "29_29") (pintype "passive"))
      (node (ref "U1") (pin "4") (pinfunction "RESB_4") (pintype "input"))
    )
    (net (code "102") (name "RW") (class "Default")
      (node (ref "IC11") (pin "13") (pinfunction "R/~{W}_13") (pintype "input"))
      (node (ref "SV1") (pin "36") (pinfunction "36_36") (pintype "passive"))
      (node (ref "U1") (pin "28") (pinfunction "R/WB_28") (pintype "input"))
    )
    (net (code "103") (name "SBY") (class "Default")
      (node (ref "IC1") (pin "14") (pinfunction "B5_14") (pintype "bidirectional"))
      (node (ref "R3") (pin "2") (pinfunction "2_2") (pintype "passive"))
      (node (ref "U$1") (pin "8") (pinfunction "SBY_8") (pintype "bidirectional"))
    )
    (net (code "104") (name "SP0256_CS") (class "Default")
      (node (ref "IC5") (pin "16") (pinfunction "O4_16") (pintype "output"))
      (node (ref "U$1") (pin "20") (pinfunction "~{ALO}_20") (pintype "bidirectional"))
    )
    (net (code "105") (name "SPO_RESET") (class "Default")
      (node (ref "C11") (pin "1") (pinfunction "1_1") (pintype "passive"))
      (node (ref "C9") (pin "1") (pinfunction "1_1") (pintype "passive"))
      (node (ref "D1") (pin "A") (pinfunction "A_A") (pintype "passive"))
      (node (ref "D2") (pin "A") (pinfunction "A_A") (pintype "passive"))
      (node (ref "R2") (pin "1") (pinfunction "1_1") (pintype "passive"))
      (node (ref "R7") (pin "1") (pinfunction "1_1") (pintype "passive"))
      (node (ref "U$1") (pin "2") (pinfunction "~{RESET}_2") (pintype "bidirectional"))
      (node (ref "U$1") (pin "25") (pinfunction "~{SBY_RESET}_25") (pintype "bidirectional"))
    )
    (net (code "106") (name "TIMER_CS") (class "Default")
      (node (ref "IC11") (pin "15") (pinfunction "CS0_15") (pintype "input"))
      (node (ref "IC5") (pin "18") (pinfunction "O2_18") (pintype "output"))
    )
    (net (code "107") (name "UART_CLK") (class "Default")
      (node (ref "QG1") (pin "8") (pinfunction "OUT_8") (pintype "output"))
      (node (ref "U1") (pin "6") (pinfunction "XTL1_6") (pintype "input"))
    )
    (net (code "108") (name "UART_CS") (class "Default")
      (node (ref "IC5") (pin "19") (pinfunction "O1_19") (pintype "output"))
      (node (ref "U1") (pin "3") (pinfunction "CS1B_3") (pintype "input"))
    )
    (net (code "109") (name "VCC") (class "Default")
      (node (ref "C1") (pin "1") (pinfunction "1_1") (pintype "passive"))
      (node (ref "C10") (pin "+") (pinfunction "+_+") (pintype "passive"))
      (node (ref "C12") (pin "2") (pinfunction "2_2") (pintype "passive"))
      (node (ref "C14") (pin "1") (pinfunction "1_1") (pintype "passive"))
      (node (ref "C16") (pin "1") (pinfunction "1_1") (pintype "passive"))
      (node (ref "C17") (pin "1") (pinfunction "1_1") (pintype "passive"))
      (node (ref "C19") (pin "1") (pinfunction "1_1") (pintype "passive"))
      (node (ref "C2") (pin "1") (pinfunction "1_1") (pintype "passive"))
      (node (ref "C21") (pin "+") (pinfunction "+_+") (pintype "passive"))
      (node (ref "C22") (pin "2") (pinfunction "2_2") (pintype "passive"))
      (node (ref "C3") (pin "1") (pinfunction "1_1") (pintype "passive"))
      (node (ref "C33") (pin "+") (pinfunction "+_+") (pintype "passive"))
      (node (ref "C6") (pin "2") (pinfunction "2_2") (pintype "passive"))
      (node (ref "D1") (pin "C") (pinfunction "C_C") (pintype "passive"))
      (node (ref "IC1") (pin "20") (pinfunction "VCC_20") (pintype "power_in"))
      (node (ref "IC11") (pin "14") (pinfunction "VCC_14") (pintype "power_in"))
      (node (ref "IC2") (pin "16") (pinfunction "VCC_16") (pintype "power_in"))
      (node (ref "IC5") (pin "20") (pinfunction "VCC_20") (pintype "power_in"))
      (node (ref "IC7") (pin "3") (pinfunction "VO_3") (pintype "passive"))
      (node (ref "JP4") (pin "4") (pinfunction "4_4") (pintype "passive"))
      (node (ref "JP4") (pin "5") (pinfunction "5_5") (pintype "passive"))
      (node (ref "JP9") (pin "3") (pinfunction "3_3") (pintype "passive"))
      (node (ref "QG1") (pin "14") (pinfunction "VCC_14") (pintype "power_in"))
      (node (ref "R1") (pin "2") (pinfunction "2_2") (pintype "passive"))
      (node (ref "R10") (pin "1") (pinfunction "1_1") (pintype "passive"))
      (node (ref "R15") (pin "2") (pinfunction "2_2") (pintype "passive"))
      (node (ref "R18") (pin "1") (pinfunction "1_1") (pintype "passive"))
      (node (ref "R19") (pin "1") (pinfunction "1_1") (pintype "passive"))
      (node (ref "R2") (pin "2") (pinfunction "2_2") (pintype "passive"))
      (node (ref "R5") (pin "1") (pinfunction "1_1") (pintype "passive"))
      (node (ref "RN1") (pin "1") (pinfunction "1_1") (pintype "passive"))
      (node (ref "T2") (pin "E") (pinfunction "E_E") (pintype "passive"))
      (node (ref "T3") (pin "C") (pinfunction "C_C") (pintype "passive"))
      (node (ref "U$1") (pin "19") (pinfunction "SE_19") (pintype "bidirectional"))
      (node (ref "U$1") (pin "23") (pinfunction "VDI_23") (pintype "bidirectional"))
      (node (ref "U$1") (pin "7") (pinfunction "VDD_7") (pintype "bidirectional"))
      (node (ref "U1") (pin "15") (pinfunction "VDD_15") (pintype "power_in"))
    )
    (net (code "110") (name "WR") (class "Default")
      (node (ref "IC5") (pin "7") (pinfunction "I6_7") (pintype "input"))
      (node (ref "SV1") (pin "34") (pinfunction "34_34") (pintype "passive"))
    )
    (net (code "111") (name "unconnected-(IC2A-R2OUT-Pad9)") (class "Default")
      (node (ref "IC2") (pin "9") (pinfunction "R2OUT_9") (pintype "output"))
    )
    (net (code "112") (name "unconnected-(IC2A-T2IN-Pad10)") (class "Default")
      (node (ref "IC2") (pin "10") (pinfunction "T2IN_10") (pintype "input"))
    )
    (net (code "113") (name "unconnected-(IC5-CLK-Pad1)") (class "Default")
      (node (ref "IC5") (pin "1") (pinfunction "CLK_1") (pintype "input"))
    )
    (net (code "114") (name "unconnected-(IC5-I8-Pad9)") (class "Default")
      (node (ref "IC5") (pin "9") (pinfunction "I8_9") (pintype "input"))
    )
    (net (code "115") (name "unconnected-(IC5-O6-Pad14)") (class "Default")
      (node (ref "IC5") (pin "14") (pinfunction "O6_14") (pintype "output"))
    )
    (net (code "116") (name "unconnected-(IC5-O7-Pad13)") (class "Default")
      (node (ref "IC5") (pin "13") (pinfunction "O7_13") (pintype "output"))
    )
    (net (code "117") (name "unconnected-(IC5-O8-Pad12)") (class "Default")
      (node (ref "IC5") (pin "12") (pinfunction "O8_12") (pintype "output"))
    )
    (net (code "118") (name "unconnected-(IC5-OE-Pad11)") (class "Default")
      (node (ref "IC5") (pin "11") (pinfunction "OE_11") (pintype "input"))
    )
    (net (code "119") (name "unconnected-(IC11A-O1-Pad27)") (class "Default")
      (node (ref "IC11") (pin "27") (pinfunction "O1_27") (pintype "output"))
    )
    (net (code "120") (name "unconnected-(JP2-Pad1)") (class "Default")
      (node (ref "JP2") (pin "1") (pinfunction "1_1") (pintype "passive"))
    )
    (net (code "121") (name "unconnected-(JP2-Pad4)") (class "Default")
      (node (ref "JP2") (pin "4") (pinfunction "4_4") (pintype "passive"))
    )
    (net (code "122") (name "unconnected-(JP2-Pad6)") (class "Default")
      (node (ref "JP2") (pin "6") (pinfunction "6_6") (pintype "passive"))
    )
    (net (code "123") (name "unconnected-(JP2-Pad9)") (class "Default")
      (node (ref "JP2") (pin "9") (pinfunction "9_9") (pintype "passive"))
    )
    (net (code "124") (name "unconnected-(JP2-Pad10)") (class "Default")
      (node (ref "JP2") (pin "10") (pinfunction "10_10") (pintype "passive"))
    )
    (net (code "125") (name "unconnected-(U$1-C1-Pad4)") (class "Default")
      (node (ref "U$1") (pin "4") (pinfunction "C1_4") (pintype "bidirectional"))
    )
    (net (code "126") (name "unconnected-(U$1-C2-Pad5)") (class "Default")
      (node (ref "U$1") (pin "5") (pinfunction "C2_5") (pintype "bidirectional"))
    )
    (net (code "127") (name "unconnected-(U$1-C3-Pad6)") (class "Default")
      (node (ref "U$1") (pin "6") (pinfunction "C3_6") (pintype "bidirectional"))
    )
    (net (code "128") (name "unconnected-(U$1-ROM_CLOCK-Pad26)") (class "Default")
      (node (ref "U$1") (pin "26") (pinfunction "ROM_CLOCK_26") (pintype "bidirectional"))
    )
    (net (code "129") (name "unconnected-(U$1-ROM_DISABLE-Pad3)") (class "Default")
      (node (ref "U$1") (pin "3") (pinfunction "ROM_DISABLE_3") (pintype "bidirectional"))
    )
    (net (code "130") (name "unconnected-(U$1-SER_IN-Pad21)") (class "Default")
      (node (ref "U$1") (pin "21") (pinfunction "SER_IN_21") (pintype "bidirectional"))
    )
    (net (code "131") (name "unconnected-(U$1-SER_OUT-Pad12)") (class "Default")
      (node (ref "U$1") (pin "12") (pinfunction "SER_OUT_12") (pintype "bidirectional"))
    )
    (net (code "132") (name "unconnected-(U1-DTR-Pad11)") (class "Default")
      (node (ref "U1") (pin "11") (pinfunction "DTR_11") (pintype "output"))
    )
    (net (code "133") (name "unconnected-(U1-RTS-Pad8)") (class "Default")
      (node (ref "U1") (pin "8") (pinfunction "RTS_8") (pintype "output"))
    )
    (net (code "134") (name "unconnected-(U1-RXCLK-Pad5)") (class "Default")
      (node (ref "U1") (pin "5") (pinfunction "RXCLK_5") (pintype "bidirectional"))
    )
    (net (code "135") (name "unconnected-(U1-XTL2-Pad7)") (class "Default")
      (node (ref "U1") (pin "7") (pinfunction "XTL2_7") (pintype "output"))
    )
  )
)
